# SDRAMPart.net
KiCad netlist of a schematic drawn in Altium Designer
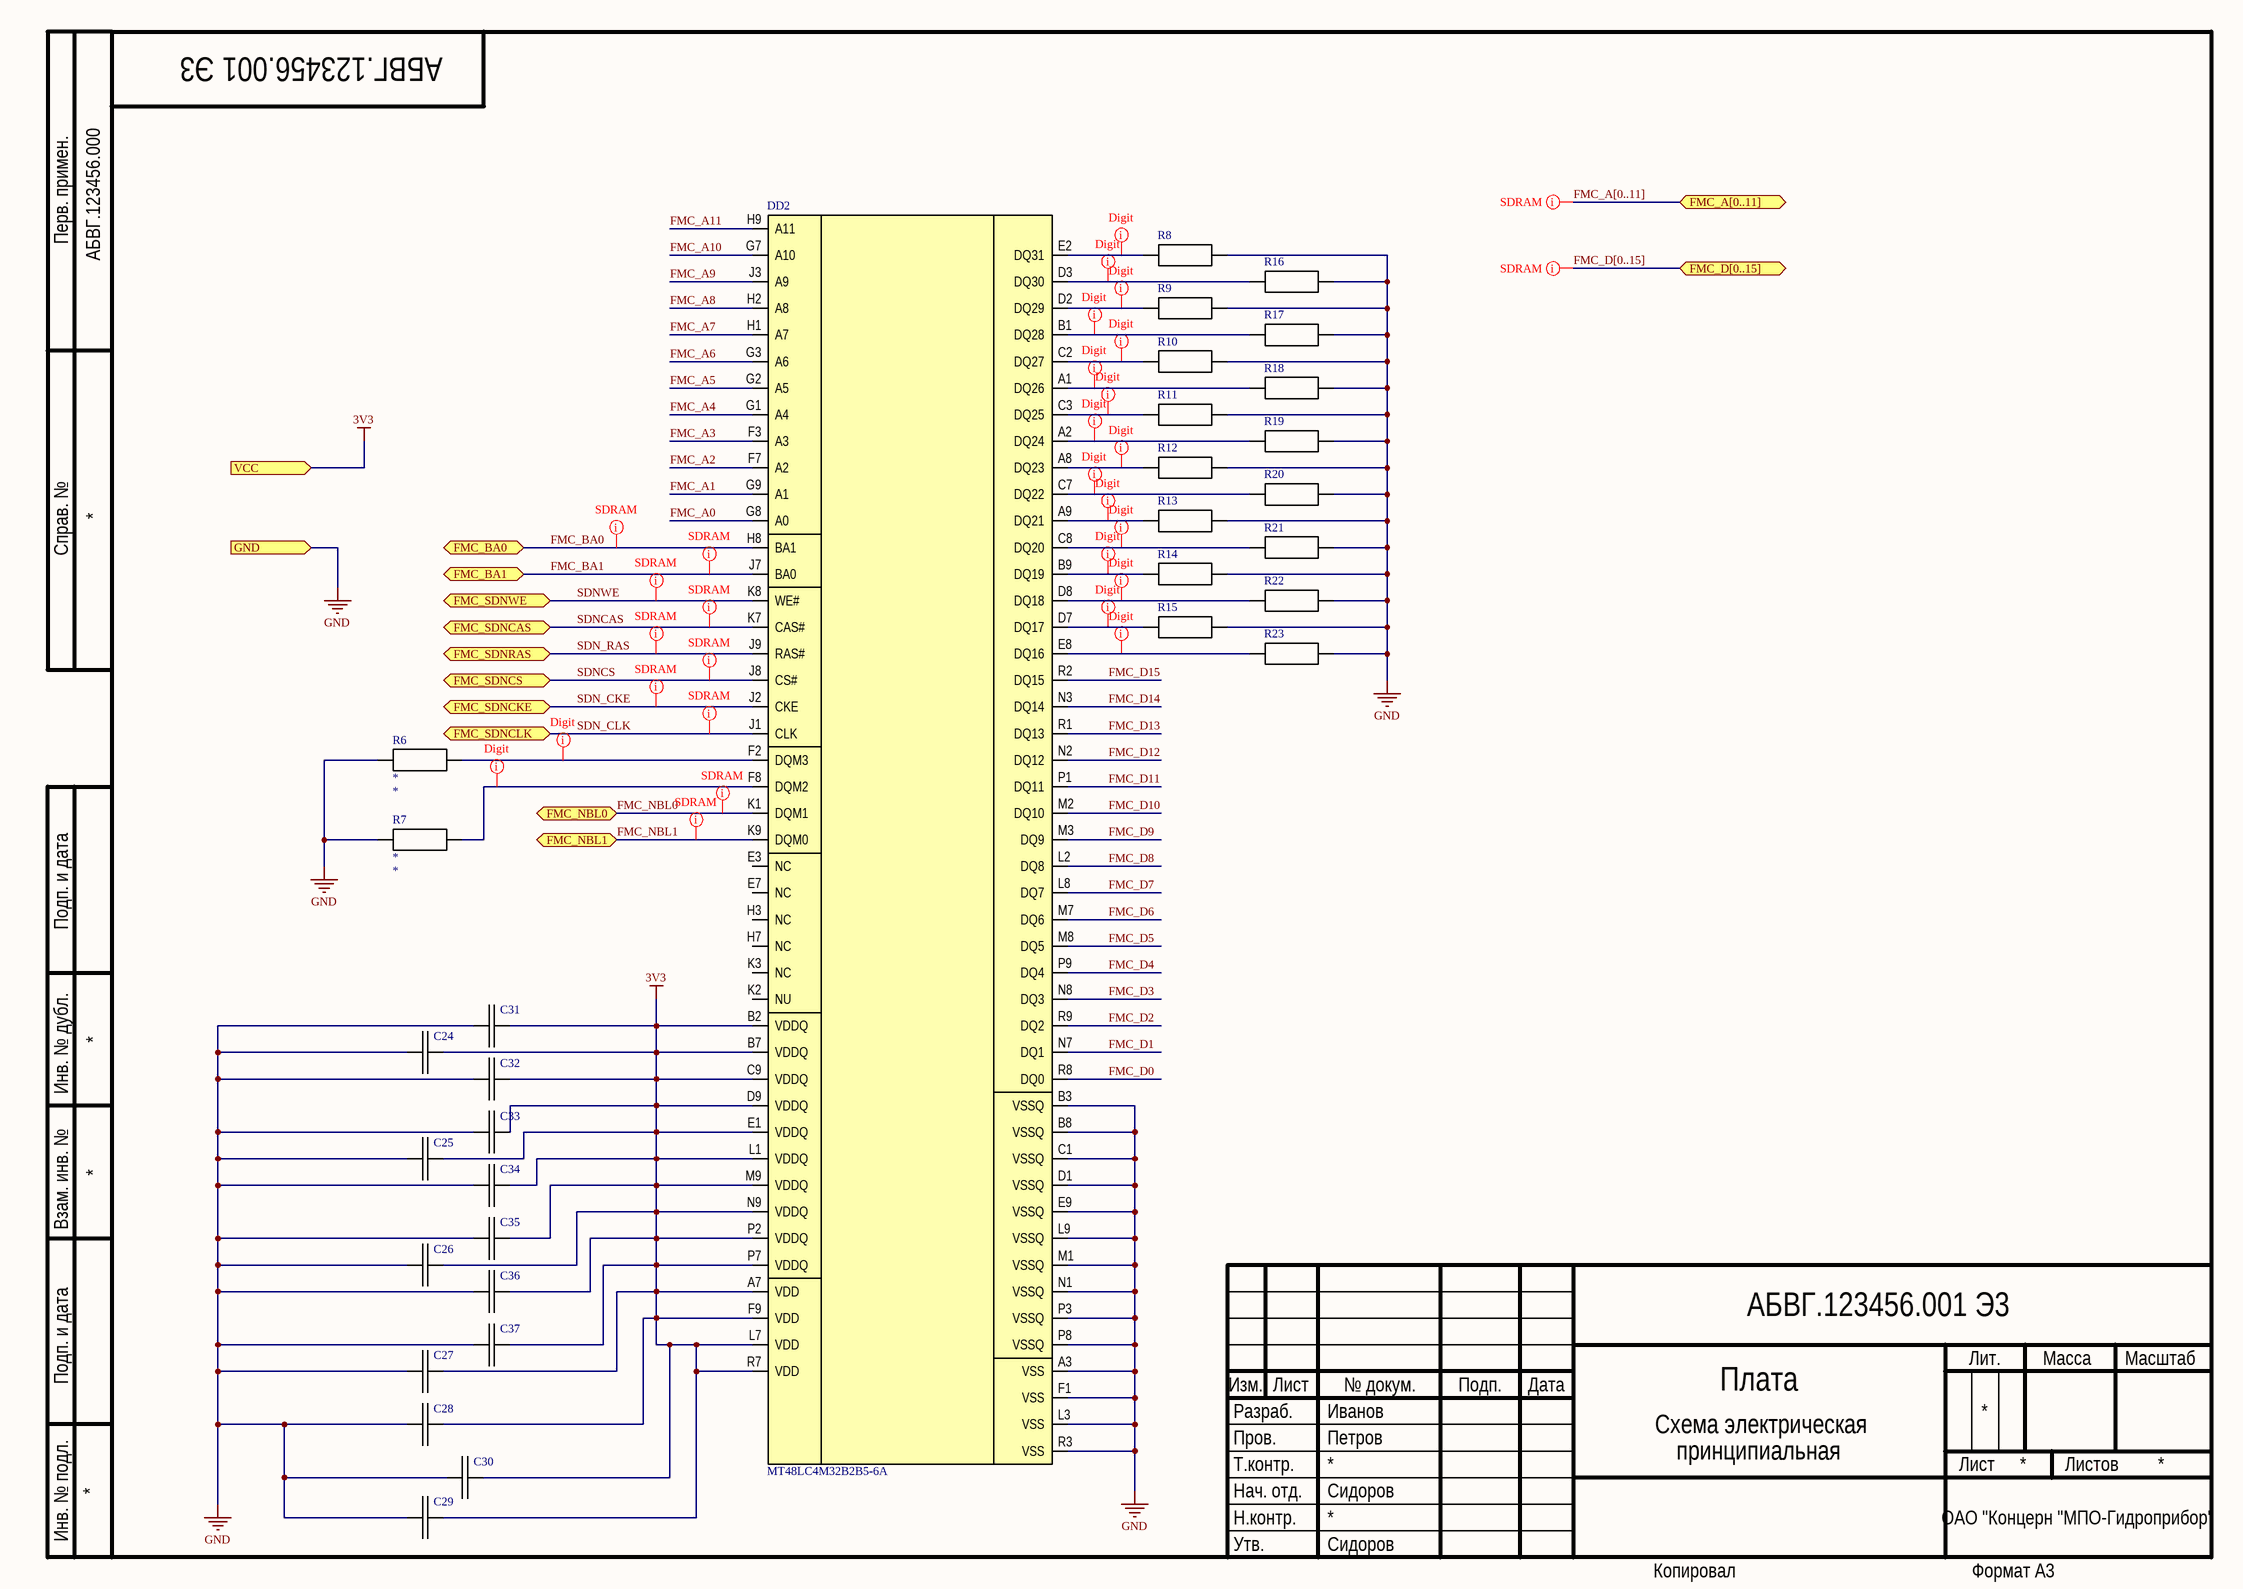
[diagram p0: SDRAMPart.SchDoc]

(export (version "E")
  (design (tool "Eeschema 10.0.6"))
  (components
    (comp (ref "C24") (value "*") (footprint "CAP1206") (libsource (lib "SchlibUGO") (part "Capasitor")))
    (comp (ref "C25") (value "*") (footprint "CAP1206") (libsource (lib "SchlibUGO") (part "Capasitor")))
    (comp (ref "C26") (value "*") (footprint "CAP1206") (libsource (lib "SchlibUGO") (part "Capasitor")))
    (comp (ref "C27") (value "*") (footprint "CAP1206") (libsource (lib "SchlibUGO") (part "Capasitor")))
    (comp (ref "C28") (value "*") (footprint "CAP1206") (libsource (lib "SchlibUGO") (part "Capasitor")))
    (comp (ref "C29") (value "*") (footprint "CAP1206") (libsource (lib "SchlibUGO") (part "Capasitor")))
    (comp (ref "C30") (value "*") (footprint "CAP1206") (libsource (lib "SchlibUGO") (part "Capasitor")))
    (comp (ref "C31") (value "*") (footprint "CAP1206") (libsource (lib "SchlibUGO") (part "Capasitor")))
    (comp (ref "C32") (value "*") (footprint "CAP1206") (libsource (lib "SchlibUGO") (part "Capasitor")))
    (comp (ref "C33") (value "*") (footprint "CAP1206") (libsource (lib "SchlibUGO") (part "Capasitor")))
    (comp (ref "C34") (value "*") (footprint "CAP1206") (libsource (lib "SchlibUGO") (part "Capasitor")))
    (comp (ref "C35") (value "*") (footprint "CAP1206") (libsource (lib "SchlibUGO") (part "Capasitor")))
    (comp (ref "C36") (value "*") (footprint "CAP1206") (libsource (lib "SchlibUGO") (part "Capasitor")))
    (comp (ref "C37") (value "*") (footprint "CAP1206") (libsource (lib "SchlibUGO") (part "Capasitor")))
    (comp (ref "DD2")
      (value "MT48LC4M32B2B5-6A")
      (footprint "VFBGA90")
      (fields (field (name "MANUFACTURER") "MICRON"))
      (libsource (lib "SchlibUGO") (part "mt48lc4m32b2b5-6a"))
    )
    (comp (ref "R6")
      (value "*")
      (footprint "1206")
      (fields (field (name "ALTIUM_VALUE") "*") (field (name "POWER") "*"))
      (libsource (lib "SchlibUGO") (part "Resistor"))
    )
    (comp (ref "R7")
      (value "*")
      (footprint "1206")
      (fields (field (name "ALTIUM_VALUE") "*") (field (name "POWER") "*"))
      (libsource (lib "SchlibUGO") (part "Resistor"))
    )
    (comp (ref "R8") (value "*") (footprint "0402") (libsource (lib "SchlibUGO") (part "Resistor")))
    (comp (ref "R9") (value "*") (footprint "0402") (libsource (lib "SchlibUGO") (part "Resistor")))
    (comp (ref "R10") (value "*") (footprint "0402") (libsource (lib "SchlibUGO") (part "Resistor")))
    (comp (ref "R11") (value "*") (footprint "0402") (libsource (lib "SchlibUGO") (part "Resistor")))
    (comp (ref "R12") (value "*") (footprint "0402") (libsource (lib "SchlibUGO") (part "Resistor")))
    (comp (ref "R13") (value "*") (footprint "0402") (libsource (lib "SchlibUGO") (part "Resistor")))
    (comp (ref "R14") (value "*") (footprint "0402") (libsource (lib "SchlibUGO") (part "Resistor")))
    (comp (ref "R15") (value "*") (footprint "0402") (libsource (lib "SchlibUGO") (part "Resistor")))
    (comp (ref "R16") (value "*") (footprint "0402") (libsource (lib "SchlibUGO") (part "Resistor")))
    (comp (ref "R17") (value "*") (footprint "0402") (libsource (lib "SchlibUGO") (part "Resistor")))
    (comp (ref "R18") (value "*") (footprint "0402") (libsource (lib "SchlibUGO") (part "Resistor")))
    (comp (ref "R19") (value "*") (footprint "0402") (libsource (lib "SchlibUGO") (part "Resistor")))
    (comp (ref "R20") (value "*") (footprint "0402") (libsource (lib "SchlibUGO") (part "Resistor")))
    (comp (ref "R21") (value "*") (footprint "0402") (libsource (lib "SchlibUGO") (part "Resistor")))
    (comp (ref "R22") (value "*") (footprint "0402") (libsource (lib "SchlibUGO") (part "Resistor")))
    (comp (ref "R23") (value "*") (footprint "0402") (libsource (lib "SchlibUGO") (part "Resistor")))
  )
  (nets
    (net (code "1") (name "/FMC_A0") (class "Default")
      (node (ref "DD2") (pin "G8") (pinfunction "A0_G8") (pintype "passive"))
    )
    (net (code "2") (name "/FMC_A1") (class "Default")
      (node (ref "DD2") (pin "G9") (pinfunction "A1_G9") (pintype "passive"))
    )
    (net (code "3") (name "/FMC_A2") (class "Default")
      (node (ref "DD2") (pin "F7") (pinfunction "A2_F7") (pintype "passive"))
    )
    (net (code "4") (name "/FMC_A3") (class "Default")
      (node (ref "DD2") (pin "F3") (pinfunction "A3_F3") (pintype "passive"))
    )
    (net (code "5") (name "/FMC_A4") (class "Default")
      (node (ref "DD2") (pin "G1") (pinfunction "A4_G1") (pintype "passive"))
    )
    (net (code "6") (name "/FMC_A5") (class "Default")
      (node (ref "DD2") (pin "G2") (pinfunction "A5_G2") (pintype "passive"))
    )
    (net (code "7") (name "/FMC_A6") (class "Default")
      (node (ref "DD2") (pin "G3") (pinfunction "A6_G3") (pintype "passive"))
    )
    (net (code "8") (name "/FMC_A7") (class "Default")
      (node (ref "DD2") (pin "H1") (pinfunction "A7_H1") (pintype "passive"))
    )
    (net (code "9") (name "/FMC_A8") (class "Default")
      (node (ref "DD2") (pin "H2") (pinfunction "A8_H2") (pintype "passive"))
    )
    (net (code "10") (name "/FMC_A9") (class "Default")
      (node (ref "DD2") (pin "J3") (pinfunction "A9_J3") (pintype "passive"))
    )
    (net (code "11") (name "/FMC_A10") (class "Default")
      (node (ref "DD2") (pin "G7") (pinfunction "A10_G7") (pintype "passive"))
    )
    (net (code "12") (name "/FMC_A11") (class "Default")
      (node (ref "DD2") (pin "H9") (pinfunction "A11_H9") (pintype "passive"))
    )
    (net (code "14") (name "/FMC_BA0") (class "Default")
      (node (ref "DD2") (pin "H8") (pinfunction "BA1_H8") (pintype "passive"))
    )
    (net (code "15") (name "/FMC_BA1") (class "Default")
      (node (ref "DD2") (pin "J7") (pinfunction "BA0_J7") (pintype "passive"))
    )
    (net (code "16") (name "/FMC_D0") (class "Default")
      (node (ref "DD2") (pin "R8") (pinfunction "DQ0_R8") (pintype "passive"))
    )
    (net (code "17") (name "/FMC_D1") (class "Default")
      (node (ref "DD2") (pin "N7") (pinfunction "DQ1_N7") (pintype "passive"))
    )
    (net (code "18") (name "/FMC_D2") (class "Default")
      (node (ref "DD2") (pin "R9") (pinfunction "DQ2_R9") (pintype "passive"))
    )
    (net (code "19") (name "/FMC_D3") (class "Default")
      (node (ref "DD2") (pin "N8") (pinfunction "DQ3_N8") (pintype "passive"))
    )
    (net (code "20") (name "/FMC_D4") (class "Default")
      (node (ref "DD2") (pin "P9") (pinfunction "DQ4_P9") (pintype "passive"))
    )
    (net (code "21") (name "/FMC_D5") (class "Default")
      (node (ref "DD2") (pin "M8") (pinfunction "DQ5_M8") (pintype "passive"))
    )
    (net (code "22") (name "/FMC_D6") (class "Default")
      (node (ref "DD2") (pin "M7") (pinfunction "DQ6_M7") (pintype "passive"))
    )
    (net (code "23") (name "/FMC_D7") (class "Default")
      (node (ref "DD2") (pin "L8") (pinfunction "DQ7_L8") (pintype "passive"))
    )
    (net (code "24") (name "/FMC_D8") (class "Default")
      (node (ref "DD2") (pin "L2") (pinfunction "DQ8_L2") (pintype "passive"))
    )
    (net (code "25") (name "/FMC_D9") (class "Default")
      (node (ref "DD2") (pin "M3") (pinfunction "DQ9_M3") (pintype "passive"))
    )
    (net (code "26") (name "/FMC_D10") (class "Default")
      (node (ref "DD2") (pin "M2") (pinfunction "DQ10_M2") (pintype "passive"))
    )
    (net (code "27") (name "/FMC_D11") (class "Default")
      (node (ref "DD2") (pin "P1") (pinfunction "DQ11_P1") (pintype "passive"))
    )
    (net (code "28") (name "/FMC_D12") (class "Default")
      (node (ref "DD2") (pin "N2") (pinfunction "DQ12_N2") (pintype "passive"))
    )
    (net (code "29") (name "/FMC_D13") (class "Default")
      (node (ref "DD2") (pin "R1") (pinfunction "DQ13_R1") (pintype "passive"))
    )
    (net (code "30") (name "/FMC_D14") (class "Default")
      (node (ref "DD2") (pin "N3") (pinfunction "DQ14_N3") (pintype "passive"))
    )
    (net (code "31") (name "/FMC_D15") (class "Default")
      (node (ref "DD2") (pin "R2") (pinfunction "DQ15_R2") (pintype "passive"))
    )
    (net (code "33") (name "/FMC_NBL0") (class "Default")
      (node (ref "DD2") (pin "K1") (pinfunction "DQM1_K1") (pintype "passive"))
    )
    (net (code "34") (name "/FMC_NBL1") (class "Default")
      (node (ref "DD2") (pin "K9") (pinfunction "DQM0_K9") (pintype "passive"))
    )
    (net (code "35") (name "/SDNCAS") (class "Default")
      (node (ref "DD2") (pin "K7") (pinfunction "CAS#_K7") (pintype "passive"))
    )
    (net (code "36") (name "/SDNCS") (class "Default")
      (node (ref "DD2") (pin "J8") (pinfunction "CS#_J8") (pintype "passive"))
    )
    (net (code "37") (name "/SDNWE") (class "Default")
      (node (ref "DD2") (pin "K8") (pinfunction "WE#_K8") (pintype "passive"))
    )
    (net (code "38") (name "/SDN_CKE") (class "Default")
      (node (ref "DD2") (pin "J2") (pinfunction "CKE_J2") (pintype "passive"))
    )
    (net (code "39") (name "/SDN_CLK") (class "Default")
      (node (ref "DD2") (pin "J1") (pinfunction "CLK_J1") (pintype "passive"))
    )
    (net (code "40") (name "/SDN_RAS") (class "Default")
      (node (ref "DD2") (pin "J9") (pinfunction "RAS#_J9") (pintype "passive"))
    )
    (net (code "41") (name "3V3") (class "Default")
      (node (ref "C24") (pin "2") (pinfunction "2_2") (pintype "passive"))
      (node (ref "C25") (pin "2") (pinfunction "2_2") (pintype "passive"))
      (node (ref "C26") (pin "2") (pinfunction "2_2") (pintype "passive"))
      (node (ref "C27") (pin "2") (pinfunction "2_2") (pintype "passive"))
      (node (ref "C28") (pin "2") (pinfunction "2_2") (pintype "passive"))
      (node (ref "C29") (pin "2") (pinfunction "2_2") (pintype "passive"))
      (node (ref "C30") (pin "2") (pinfunction "2_2") (pintype "passive"))
      (node (ref "C31") (pin "2") (pinfunction "2_2") (pintype "passive"))
      (node (ref "C32") (pin "2") (pinfunction "2_2") (pintype "passive"))
      (node (ref "C33") (pin "2") (pinfunction "2_2") (pintype "passive"))
      (node (ref "C34") (pin "2") (pinfunction "2_2") (pintype "passive"))
      (node (ref "C35") (pin "2") (pinfunction "2_2") (pintype "passive"))
      (node (ref "C36") (pin "2") (pinfunction "2_2") (pintype "passive"))
      (node (ref "C37") (pin "2") (pinfunction "2_2") (pintype "passive"))
      (node (ref "DD2") (pin "A7") (pinfunction "VDD_A7") (pintype "passive"))
      (node (ref "DD2") (pin "B2") (pinfunction "VDDQ_B2") (pintype "passive"))
      (node (ref "DD2") (pin "B7") (pinfunction "VDDQ_B7") (pintype "passive"))
      (node (ref "DD2") (pin "C9") (pinfunction "VDDQ_C9") (pintype "passive"))
      (node (ref "DD2") (pin "D9") (pinfunction "VDDQ_D9") (pintype "passive"))
      (node (ref "DD2") (pin "E1") (pinfunction "VDDQ_E1") (pintype "passive"))
      (node (ref "DD2") (pin "F9") (pinfunction "VDD_F9") (pintype "passive"))
      (node (ref "DD2") (pin "L1") (pinfunction "VDDQ_L1") (pintype "passive"))
      (node (ref "DD2") (pin "L7") (pinfunction "VDD_L7") (pintype "passive"))
      (node (ref "DD2") (pin "M9") (pinfunction "VDDQ_M9") (pintype "passive"))
      (node (ref "DD2") (pin "N9") (pinfunction "VDDQ_N9") (pintype "passive"))
      (node (ref "DD2") (pin "P2") (pinfunction "VDDQ_P2") (pintype "passive"))
      (node (ref "DD2") (pin "P7") (pinfunction "VDDQ_P7") (pintype "passive"))
      (node (ref "DD2") (pin "R7") (pinfunction "VDD_R7") (pintype "passive"))
    )
    (net (code "42") (name "GND") (class "Default")
      (node (ref "C24") (pin "1") (pinfunction "1_1") (pintype "passive"))
      (node (ref "C25") (pin "1") (pinfunction "1_1") (pintype "passive"))
      (node (ref "C26") (pin "1") (pinfunction "1_1") (pintype "passive"))
      (node (ref "C27") (pin "1") (pinfunction "1_1") (pintype "passive"))
      (node (ref "C28") (pin "1") (pinfunction "1_1") (pintype "passive"))
      (node (ref "C29") (pin "1") (pinfunction "1_1") (pintype "passive"))
      (node (ref "C30") (pin "1") (pinfunction "1_1") (pintype "passive"))
      (node (ref "C31") (pin "1") (pinfunction "1_1") (pintype "passive"))
      (node (ref "C32") (pin "1") (pinfunction "1_1") (pintype "passive"))
      (node (ref "C33") (pin "1") (pinfunction "1_1") (pintype "passive"))
      (node (ref "C34") (pin "1") (pinfunction "1_1") (pintype "passive"))
      (node (ref "C35") (pin "1") (pinfunction "1_1") (pintype "passive"))
      (node (ref "C36") (pin "1") (pinfunction "1_1") (pintype "passive"))
      (node (ref "C37") (pin "1") (pinfunction "1_1") (pintype "passive"))
      (node (ref "DD2") (pin "A3") (pinfunction "VSS_A3") (pintype "passive"))
      (node (ref "DD2") (pin "B3") (pinfunction "VSSQ_B3") (pintype "passive"))
      (node (ref "DD2") (pin "B8") (pinfunction "VSSQ_B8") (pintype "passive"))
      (node (ref "DD2") (pin "C1") (pinfunction "VSSQ_C1") (pintype "passive"))
      (node (ref "DD2") (pin "D1") (pinfunction "VSSQ_D1") (pintype "passive"))
      (node (ref "DD2") (pin "E9") (pinfunction "VSSQ_E9") (pintype "passive"))
      (node (ref "DD2") (pin "F1") (pinfunction "VSS_F1") (pintype "passive"))
      (node (ref "DD2") (pin "L3") (pinfunction "VSS_L3") (pintype "passive"))
      (node (ref "DD2") (pin "L9") (pinfunction "VSSQ_L9") (pintype "passive"))
      (node (ref "DD2") (pin "M1") (pinfunction "VSSQ_M1") (pintype "passive"))
      (node (ref "DD2") (pin "N1") (pinfunction "VSSQ_N1") (pintype "passive"))
      (node (ref "DD2") (pin "P3") (pinfunction "VSSQ_P3") (pintype "passive"))
      (node (ref "DD2") (pin "P8") (pinfunction "VSSQ_P8") (pintype "passive"))
      (node (ref "DD2") (pin "R3") (pinfunction "VSS_R3") (pintype "passive"))
      (node (ref "R10") (pin "2") (pinfunction "2_2") (pintype "passive"))
      (node (ref "R11") (pin "2") (pinfunction "2_2") (pintype "passive"))
      (node (ref "R12") (pin "2") (pinfunction "2_2") (pintype "passive"))
      (node (ref "R13") (pin "2") (pinfunction "2_2") (pintype "passive"))
      (node (ref "R14") (pin "2") (pinfunction "2_2") (pintype "passive"))
      (node (ref "R15") (pin "2") (pinfunction "2_2") (pintype "passive"))
      (node (ref "R16") (pin "2") (pinfunction "2_2") (pintype "passive"))
      (node (ref "R17") (pin "2") (pinfunction "2_2") (pintype "passive"))
      (node (ref "R18") (pin "2") (pinfunction "2_2") (pintype "passive"))
      (node (ref "R19") (pin "2") (pinfunction "2_2") (pintype "passive"))
      (node (ref "R20") (pin "2") (pinfunction "2_2") (pintype "passive"))
      (node (ref "R21") (pin "2") (pinfunction "2_2") (pintype "passive"))
      (node (ref "R22") (pin "2") (pinfunction "2_2") (pintype "passive"))
      (node (ref "R23") (pin "2") (pinfunction "2_2") (pintype "passive"))
      (node (ref "R6") (pin "1") (pinfunction "1_1") (pintype "passive"))
      (node (ref "R7") (pin "1") (pinfunction "1_1") (pintype "passive"))
      (node (ref "R8") (pin "2") (pinfunction "2_2") (pintype "passive"))
      (node (ref "R9") (pin "2") (pinfunction "2_2") (pintype "passive"))
    )
    (net (code "43") (name "Net-(DD2-DQ16)") (class "Default")
      (node (ref "DD2") (pin "E8") (pinfunction "DQ16_E8") (pintype "passive"))
      (node (ref "R23") (pin "1") (pinfunction "1_1") (pintype "passive"))
    )
    (net (code "44") (name "Net-(DD2-DQ17)") (class "Default")
      (node (ref "DD2") (pin "D7") (pinfunction "DQ17_D7") (pintype "passive"))
      (node (ref "R15") (pin "1") (pinfunction "1_1") (pintype "passive"))
    )
    (net (code "45") (name "Net-(DD2-DQ18)") (class "Default")
      (node (ref "DD2") (pin "D8") (pinfunction "DQ18_D8") (pintype "passive"))
      (node (ref "R22") (pin "1") (pinfunction "1_1") (pintype "passive"))
    )
    (net (code "46") (name "Net-(DD2-DQ19)") (class "Default")
      (node (ref "DD2") (pin "B9") (pinfunction "DQ19_B9") (pintype "passive"))
      (node (ref "R14") (pin "1") (pinfunction "1_1") (pintype "passive"))
    )
    (net (code "47") (name "Net-(DD2-DQ20)") (class "Default")
      (node (ref "DD2") (pin "C8") (pinfunction "DQ20_C8") (pintype "passive"))
      (node (ref "R21") (pin "1") (pinfunction "1_1") (pintype "passive"))
    )
    (net (code "48") (name "Net-(DD2-DQ21)") (class "Default")
      (node (ref "DD2") (pin "A9") (pinfunction "DQ21_A9") (pintype "passive"))
      (node (ref "R13") (pin "1") (pinfunction "1_1") (pintype "passive"))
    )
    (net (code "49") (name "Net-(DD2-DQ22)") (class "Default")
      (node (ref "DD2") (pin "C7") (pinfunction "DQ22_C7") (pintype "passive"))
      (node (ref "R20") (pin "1") (pinfunction "1_1") (pintype "passive"))
    )
    (net (code "50") (name "Net-(DD2-DQ23)") (class "Default")
      (node (ref "DD2") (pin "A8") (pinfunction "DQ23_A8") (pintype "passive"))
      (node (ref "R12") (pin "1") (pinfunction "1_1") (pintype "passive"))
    )
    (net (code "51") (name "Net-(DD2-DQ24)") (class "Default")
      (node (ref "DD2") (pin "A2") (pinfunction "DQ24_A2") (pintype "passive"))
      (node (ref "R19") (pin "1") (pinfunction "1_1") (pintype "passive"))
    )
    (net (code "52") (name "Net-(DD2-DQ25)") (class "Default")
      (node (ref "DD2") (pin "C3") (pinfunction "DQ25_C3") (pintype "passive"))
      (node (ref "R11") (pin "1") (pinfunction "1_1") (pintype "passive"))
    )
    (net (code "53") (name "Net-(DD2-DQ26)") (class "Default")
      (node (ref "DD2") (pin "A1") (pinfunction "DQ26_A1") (pintype "passive"))
      (node (ref "R18") (pin "1") (pinfunction "1_1") (pintype "passive"))
    )
    (net (code "54") (name "Net-(DD2-DQ27)") (class "Default")
      (node (ref "DD2") (pin "C2") (pinfunction "DQ27_C2") (pintype "passive"))
      (node (ref "R10") (pin "1") (pinfunction "1_1") (pintype "passive"))
    )
    (net (code "55") (name "Net-(DD2-DQ28)") (class "Default")
      (node (ref "DD2") (pin "B1") (pinfunction "DQ28_B1") (pintype "passive"))
      (node (ref "R17") (pin "1") (pinfunction "1_1") (pintype "passive"))
    )
    (net (code "56") (name "Net-(DD2-DQ29)") (class "Default")
      (node (ref "DD2") (pin "D2") (pinfunction "DQ29_D2") (pintype "passive"))
      (node (ref "R9") (pin "1") (pinfunction "1_1") (pintype "passive"))
    )
    (net (code "57") (name "Net-(DD2-DQ30)") (class "Default")
      (node (ref "DD2") (pin "D3") (pinfunction "DQ30_D3") (pintype "passive"))
      (node (ref "R16") (pin "1") (pinfunction "1_1") (pintype "passive"))
    )
    (net (code "58") (name "Net-(DD2-DQ31)") (class "Default")
      (node (ref "DD2") (pin "E2") (pinfunction "DQ31_E2") (pintype "passive"))
      (node (ref "R8") (pin "1") (pinfunction "1_1") (pintype "passive"))
    )
    (net (code "59") (name "Net-(DD2-DQM2)") (class "Default")
      (node (ref "DD2") (pin "F8") (pinfunction "DQM2_F8") (pintype "passive"))
      (node (ref "R7") (pin "2") (pinfunction "2_2") (pintype "passive"))
    )
    (net (code "60") (name "Net-(DD2-DQM3)") (class "Default")
      (node (ref "DD2") (pin "F2") (pinfunction "DQM3_F2") (pintype "passive"))
      (node (ref "R6") (pin "2") (pinfunction "2_2") (pintype "passive"))
    )
    (net (code "61") (name "unconnected-(DD2-NC-PadE3)") (class "Default")
      (node (ref "DD2") (pin "E3") (pinfunction "NC_E3") (pintype "passive"))
    )
    (net (code "62") (name "unconnected-(DD2-NC-PadE7)") (class "Default")
      (node (ref "DD2") (pin "E7") (pinfunction "NC_E7") (pintype "passive"))
    )
    (net (code "63") (name "unconnected-(DD2-NC-PadH3)") (class "Default")
      (node (ref "DD2") (pin "H3") (pinfunction "NC_H3") (pintype "passive"))
    )
    (net (code "64") (name "unconnected-(DD2-NC-PadH7)") (class "Default")
      (node (ref "DD2") (pin "H7") (pinfunction "NC_H7") (pintype "passive"))
    )
    (net (code "65") (name "unconnected-(DD2-NC-PadK3)") (class "Default")
      (node (ref "DD2") (pin "K3") (pinfunction "NC_K3") (pintype "passive"))
    )
    (net (code "66") (name "unconnected-(DD2-NU-PadK2)") (class "Default")
      (node (ref "DD2") (pin "K2") (pinfunction "NU_K2") (pintype "passive"))
    )
  )
)
